# 5-POWER.net
KiCad netlist of a schematic drawn in Altium Designer
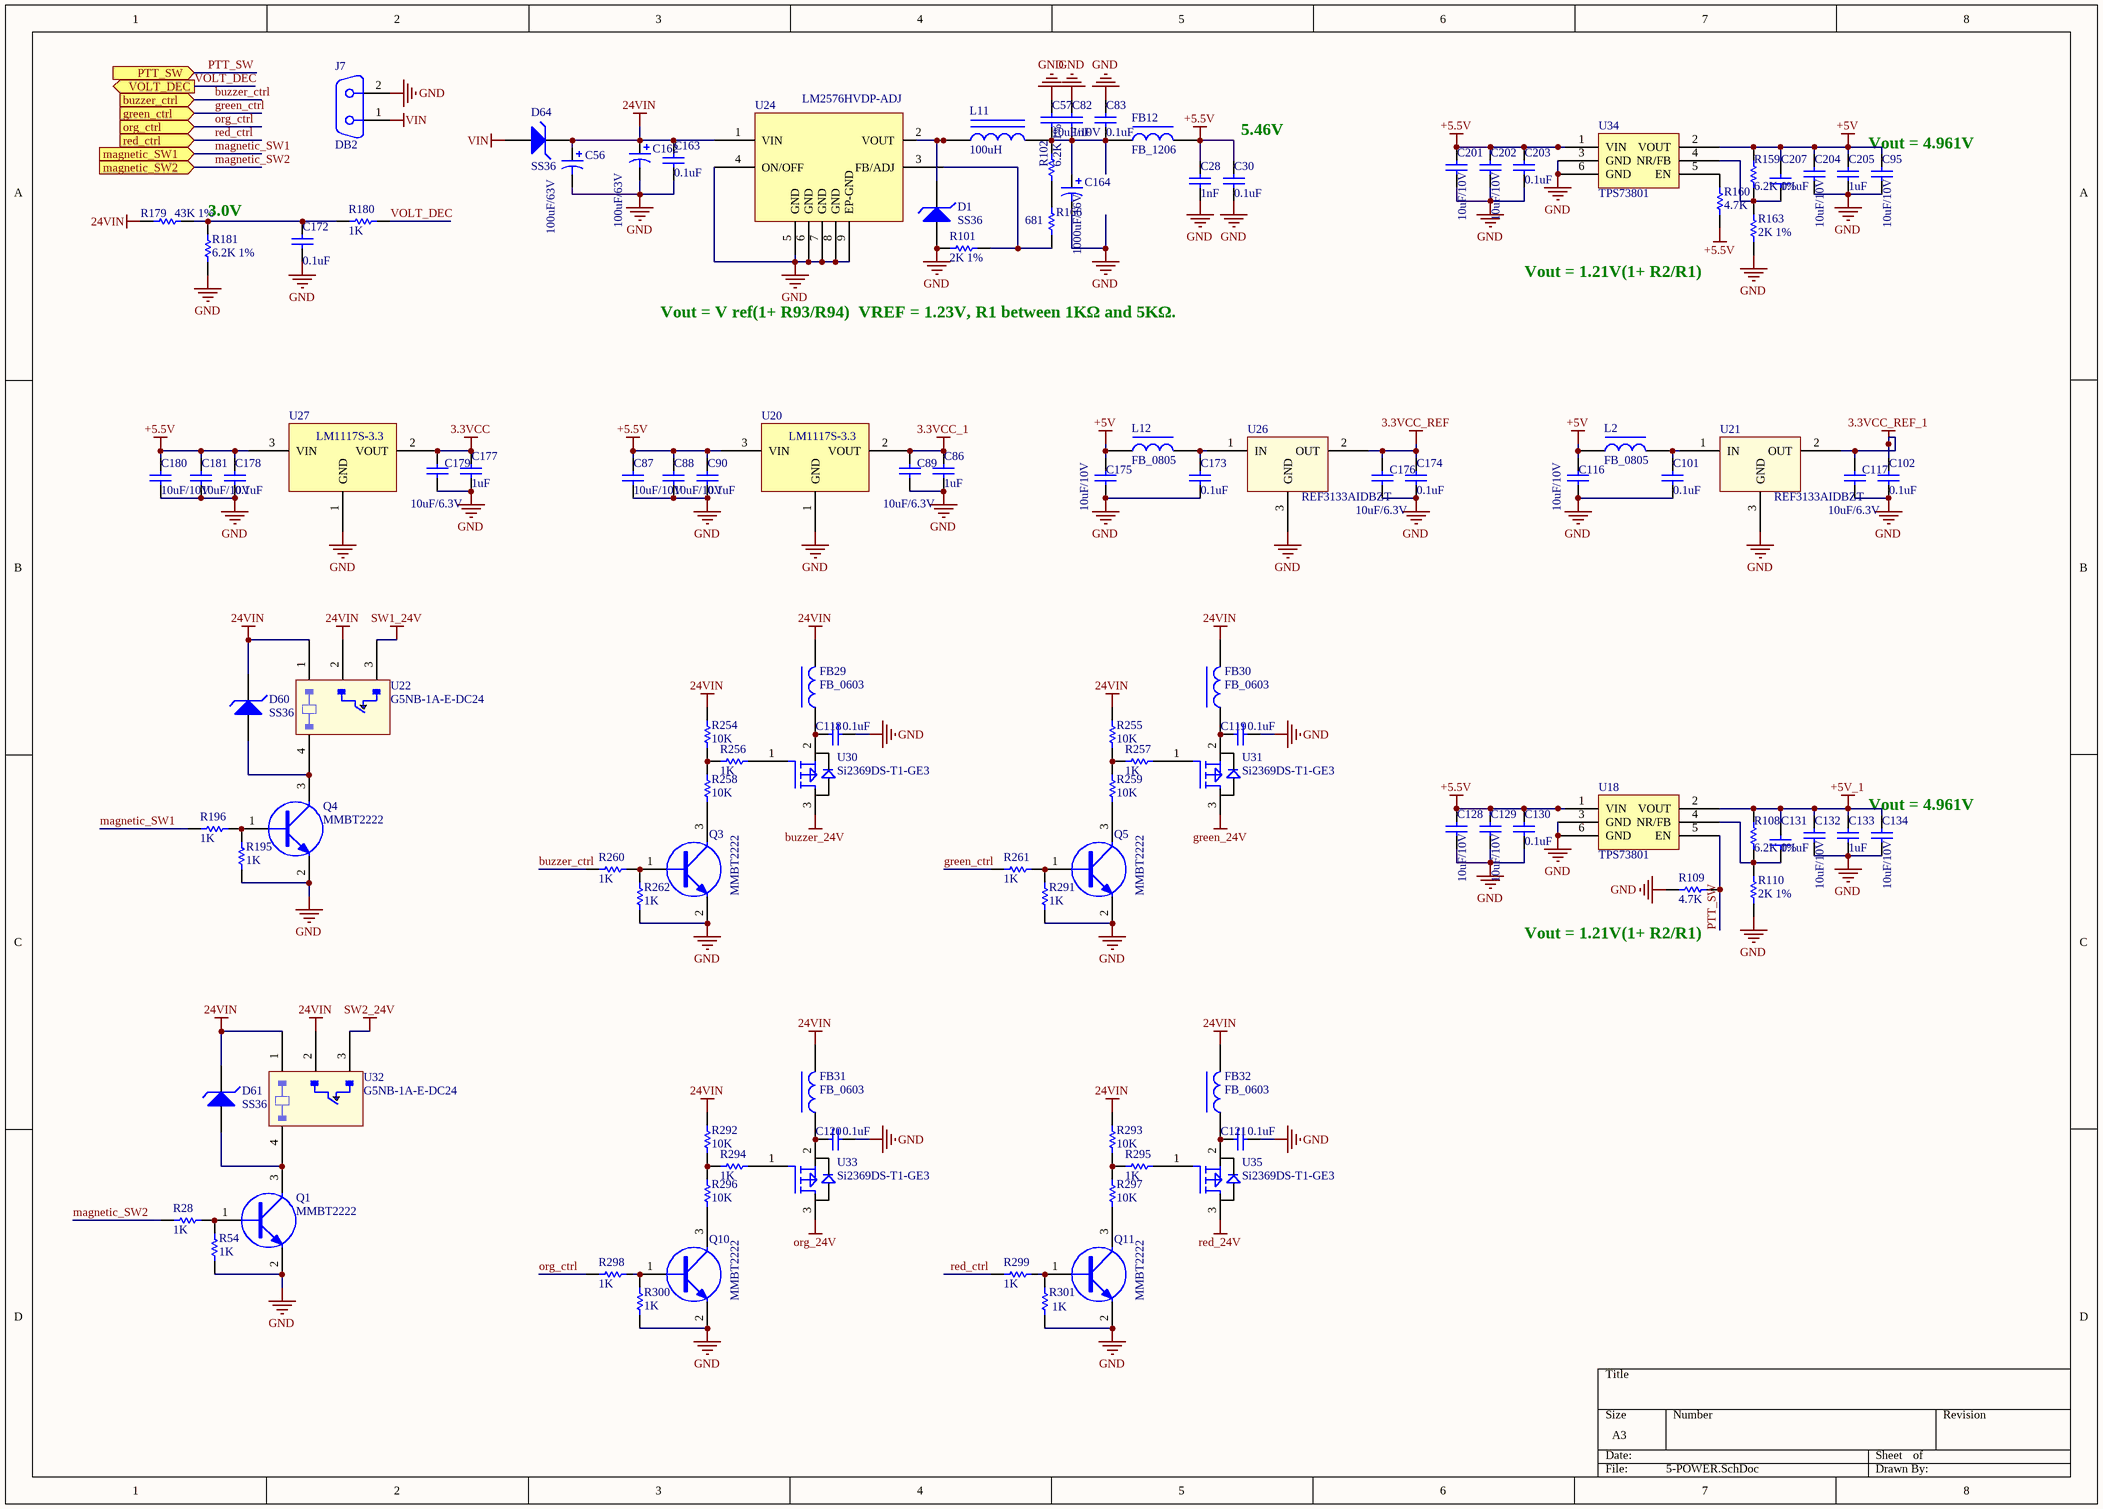
[diagram p0: 5-POWER.SchDoc]

(export (version "E")
  (design (tool "Eeschema 10.0.6"))
  (components
    (comp (ref "C28")
      (value "1nF")
      (footprint "C0603")
      (description "贴片电容_GRM188R71H102KA01_1000pF±10%,50V,0603")
      (libsource (lib "20贴片电容0603") (part "1000pF贴片电容"))
    )
    (comp (ref "C30")
      (value "0.1uF")
      (footprint "C0603")
      (description "GRM188R71H104KA01D")
      (fields (field (name "MPN") "MURATA"))
      (libsource (lib "20贴片电容0603") (part "0.1uF"))
    )
    (comp (ref "C56")
      (value "100uF/63V")
      (footprint "ECAP2SM_10R4x10R4")
      (description "电解电容_VEJ101M1JTR-1010_100uF/63V,±20%,表贴10*10")
      (libsource (lib "23电解电容") (part "100uF/63V电解电容"))
    )
    (comp (ref "C57")
      (value "10uF/10V")
      (footprint "C0805")
      (description "贴片电容_GRM21BR61A106KE19L_10uF±10%,10V,0805")
      (libsource (lib "21贴片电容0805") (part "10uF贴片电容"))
    )
    (comp (ref "C82")
      (value "1nF")
      (footprint "C0603")
      (description "贴片电容_GRM188R71H102KA01_1000pF±10%,50V,0603")
      (libsource (lib "20贴片电容0603") (part "1000pF贴片电容"))
    )
    (comp (ref "C83")
      (value "0.1uF")
      (footprint "C0603")
      (description "GRM188R71H104KA01D")
      (fields (field (name "MPN") "MURATA"))
      (libsource (lib "20贴片电容0603") (part "0.1uF"))
    )
    (comp (ref "C86")
      (value "1uF")
      (footprint "C0603")
      (description "贴片电容_GRM188R61A105KA61D_1uF±10%,10V,0603")
      (libsource (lib "20贴片电容0603") (part "1uF贴片电容"))
    )
    (comp (ref "C87")
      (value "10uF/10V")
      (footprint "C0805")
      (description "贴片电容_GRM21BR61A106KE19L_10uF±10%,10V,0805")
      (libsource (lib "21贴片电容0805") (part "10uF贴片电容"))
    )
    (comp (ref "C88")
      (value "10uF/10V")
      (footprint "C0805")
      (description "贴片电容_GRM21BR61A106KE19L_10uF±10%,10V,0805")
      (libsource (lib "21贴片电容0805") (part "10uF贴片电容"))
    )
    (comp (ref "C89")
      (value "10uF/6.3V")
      (footprint "C0603")
      (description "贴片电容_GRM188R60J106ME47D_10uF±20%,6.3V,0603")
      (libsource (lib "20贴片电容0603") (part "10uF贴片电容"))
    )
    (comp (ref "C90")
      (value "0.1uF")
      (footprint "C0603")
      (description "贴片电容_GRM188R71H104KA01D_0.1uF±10%,50V,0603")
      (libsource (lib "20贴片电容0603") (part "0.1uF贴片电容"))
    )
    (comp (ref "C95")
      (value "10uF/10V")
      (footprint "C0805")
      (description "贴片电容_GRM21BR61A106KE19L_10uF±10%,10V,0805")
      (libsource (lib "21贴片电容0805") (part "10uF贴片电容"))
    )
    (comp (ref "C101")
      (value "0.1uF")
      (footprint "C0603")
      (description "贴片电容_GRM188R71H104KA01D_0.1uF±10%,50V,0603")
      (libsource (lib "20贴片电容0603") (part "0.1uF贴片电容"))
    )
    (comp (ref "C102")
      (value "0.1uF")
      (footprint "C0603")
      (description "贴片电容_GRM188R71H104KA01D_0.1uF±10%,50V,0603")
      (libsource (lib "20贴片电容0603") (part "0.1uF贴片电容"))
    )
    (comp (ref "C116")
      (value "10uF/10V")
      (footprint "pcblib:C0805")
      (description "贴片电容_GRM21BR61A106KE19L_10uF±10%,10V,0805")
      (libsource (lib "21贴片电容0805") (part "10uF贴片电容"))
    )
    (comp (ref "C117")
      (value "10uF/6.3V")
      (footprint "C0603")
      (description "贴片电容_GRM188R60J106ME47D_10uF±20%,6.3V,0603")
      (libsource (lib "20贴片电容0603") (part "10uF贴片电容"))
    )
    (comp (ref "C118")
      (value "0.1uF")
      (footprint "C0603")
      (description "GRM188R71H104KA01D")
      (fields (field (name "MPN") "MURATA"))
      (libsource (lib "20贴片电容0603") (part "0.1uF"))
    )
    (comp (ref "C119")
      (value "0.1uF")
      (footprint "C0603")
      (description "GRM188R71H104KA01D")
      (fields (field (name "MPN") "MURATA"))
      (libsource (lib "20贴片电容0603") (part "0.1uF"))
    )
    (comp (ref "C120")
      (value "0.1uF")
      (footprint "C0603")
      (description "GRM188R71H104KA01D")
      (fields (field (name "MPN") "MURATA"))
      (libsource (lib "20贴片电容0603") (part "0.1uF"))
    )
    (comp (ref "C121")
      (value "0.1uF")
      (footprint "C0603")
      (description "GRM188R71H104KA01D")
      (fields (field (name "MPN") "MURATA"))
      (libsource (lib "20贴片电容0603") (part "0.1uF"))
    )
    (comp (ref "C128")
      (value "10uF/10V")
      (footprint "pcblib:C0805")
      (description "贴片电容_GRM21BR61A106KE19L_10uF±10%,10V,0805")
      (libsource (lib "21贴片电容0805") (part "10uF贴片电容"))
    )
    (comp (ref "C129")
      (value "10uF/10V")
      (footprint "pcblib:C0805")
      (description "贴片电容_GRM21BR61A106KE19L_10uF±10%,10V,0805")
      (libsource (lib "21贴片电容0805") (part "10uF贴片电容"))
    )
    (comp (ref "C130")
      (value "0.1uF")
      (footprint "C0603")
      (description "贴片电容_GRM188R71H104KA01D_0.1uF±10%,50V,0603")
      (libsource (lib "20贴片电容0603") (part "0.1uF贴片电容"))
    )
    (comp (ref "C131")
      (value "0.1uF")
      (footprint "C0603")
      (description "贴片电容_GRM188R71H104KA01D_0.1uF±10%,50V,0603")
      (libsource (lib "20贴片电容0603") (part "0.1uF贴片电容"))
    )
    (comp (ref "C132")
      (value "10uF/10V")
      (footprint "pcblib:C0805")
      (description "贴片电容_GRM21BR61A106KE19L_10uF±10%,10V,0805")
      (libsource (lib "21贴片电容0805") (part "10uF贴片电容"))
    )
    (comp (ref "C133")
      (value "1uF")
      (footprint "C0603")
      (description "贴片电容_GRM188R61A105KA61D_1uF±10%,10V,0603")
      (libsource (lib "20贴片电容0603") (part "1uF贴片电容"))
    )
    (comp (ref "C134")
      (value "10uF/10V")
      (footprint "pcblib:C0805")
      (description "贴片电容_GRM21BR61A106KE19L_10uF±10%,10V,0805")
      (libsource (lib "21贴片电容0805") (part "10uF贴片电容"))
    )
    (comp (ref "C162")
      (value "100uF/63V")
      (footprint "ECAP2SM_10R4x10R4")
      (description "电解电容_VEJ101M1JTR-1010_100uF/63V,±20%,表贴10*10")
      (libsource (lib "23电解电容") (part "100uF/63V电解电容"))
    )
    (comp (ref "C163")
      (value "0.1uF")
      (footprint "C0603")
      (description "贴片电容_GRM188R71H104KA01D_0.1uF±10%,50V,0603")
      (libsource (lib "20贴片电容0603") (part "0.1uF贴片电容"))
    )
    (comp (ref "C164")
      (value "1000uF/16V")
      (footprint "ECAP2SM_10R4x10R4")
      (description "电解电容_VE102M1CTR-1010_1000uF/16V,±20%,表贴10*10")
      (libsource (lib "23电解电容") (part "1000uF/16V电解电容"))
    )
    (comp (ref "C172")
      (value "0.1uF")
      (footprint "C0603")
      (description "贴片电容_GRM188R71H104KA01D_0.1uF±10%,50V,0603")
      (libsource (lib "20贴片电容0603") (part "0.1uF贴片电容"))
    )
    (comp (ref "C173")
      (value "0.1uF")
      (footprint "C0603")
      (description "贴片电容_GRM188R71H104KA01D_0.1uF±10%,50V,0603")
      (libsource (lib "20贴片电容0603") (part "0.1uF贴片电容"))
    )
    (comp (ref "C174")
      (value "0.1uF")
      (footprint "C0603")
      (description "贴片电容_GRM188R71H104KA01D_0.1uF±10%,50V,0603")
      (libsource (lib "20贴片电容0603") (part "0.1uF贴片电容"))
    )
    (comp (ref "C175")
      (value "10uF/10V")
      (footprint "C0805")
      (description "贴片电容_GRM21BR61A106KE19L_10uF±10%,10V,0805")
      (libsource (lib "21贴片电容0805") (part "10uF贴片电容"))
    )
    (comp (ref "C176")
      (value "10uF/6.3V")
      (footprint "C0603")
      (description "贴片电容_GRM188R60J106ME47D_10uF±20%,6.3V,0603")
      (libsource (lib "20贴片电容0603") (part "10uF贴片电容"))
    )
    (comp (ref "C177")
      (value "1uF")
      (footprint "C0603")
      (description "贴片电容_GRM188R61A105KA61D_1uF±10%,10V,0603")
      (libsource (lib "20贴片电容0603") (part "1uF贴片电容"))
    )
    (comp (ref "C178")
      (value "0.1uF")
      (footprint "C0603")
      (description "贴片电容_GRM188R71H104KA01D_0.1uF±10%,50V,0603")
      (libsource (lib "20贴片电容0603") (part "0.1uF贴片电容"))
    )
    (comp (ref "C179")
      (value "10uF/6.3V")
      (footprint "C0603")
      (description "贴片电容_GRM188R60J106ME47D_10uF±20%,6.3V,0603")
      (libsource (lib "20贴片电容0603") (part "10uF贴片电容"))
    )
    (comp (ref "C180")
      (value "10uF/10V")
      (footprint "C0805")
      (description "贴片电容_GRM21BR61A106KE19L_10uF±10%,10V,0805")
      (libsource (lib "21贴片电容0805") (part "10uF贴片电容"))
    )
    (comp (ref "C181")
      (value "10uF/10V")
      (footprint "C0805")
      (description "贴片电容_GRM21BR61A106KE19L_10uF±10%,10V,0805")
      (libsource (lib "21贴片电容0805") (part "10uF贴片电容"))
    )
    (comp (ref "C201")
      (value "10uF/10V")
      (footprint "C0805")
      (description "贴片电容_GRM21BR61A106KE19L_10uF±10%,10V,0805")
      (libsource (lib "21贴片电容0805") (part "10uF贴片电容"))
    )
    (comp (ref "C202")
      (value "10uF/10V")
      (footprint "C0805")
      (description "贴片电容_GRM21BR61A106KE19L_10uF±10%,10V,0805")
      (libsource (lib "21贴片电容0805") (part "10uF贴片电容"))
    )
    (comp (ref "C203")
      (value "0.1uF")
      (footprint "C0603")
      (description "贴片电容_GRM188R71H104KA01D_0.1uF±10%,50V,0603")
      (libsource (lib "20贴片电容0603") (part "0.1uF贴片电容"))
    )
    (comp (ref "C204")
      (value "10uF/10V")
      (footprint "C0805")
      (description "贴片电容_GRM21BR61A106KE19L_10uF±10%,10V,0805")
      (libsource (lib "21贴片电容0805") (part "10uF贴片电容"))
    )
    (comp (ref "C205")
      (value "1uF")
      (footprint "C0603")
      (description "贴片电容_GRM188R61A105KA61D_1uF±10%,10V,0603")
      (libsource (lib "20贴片电容0603") (part "1uF贴片电容"))
    )
    (comp (ref "C207")
      (value "0.1uF")
      (footprint "C0603")
      (description "贴片电容_GRM188R71H104KA01D_0.1uF±10%,50V,0603")
      (libsource (lib "20贴片电容0603") (part "0.1uF贴片电容"))
    )
    (comp (ref "D1")
      (value "SS36")
      (footprint "DO-214AC")
      (description "肖特基整流二极管_SS36_封装SMA,3A/60V")
      (libsource (lib "40二极管") (part "肖特基整流二极管_SS36"))
    )
    (comp (ref "D60")
      (value "SS36")
      (footprint "DO-214AC")
      (description "肖特基整流二极管_SS36_封装SMA,3A/60V")
      (libsource (lib "40二极管") (part "肖特基整流二极管_SS36"))
    )
    (comp (ref "D61")
      (value "SS36")
      (footprint "DO-214AC")
      (description "肖特基整流二极管_SS36_封装SMA,3A/60V")
      (libsource (lib "40二极管") (part "肖特基整流二极管_SS36"))
    )
    (comp (ref "D64")
      (value "SS36")
      (footprint "DO-214AC")
      (description "肖特基整流二极管_SS36_封装SMA,3A/60V")
      (libsource (lib "40二极管") (part "肖特基整流二极管_SS36"))
    )
    (comp (ref "FB12")
      (value "FB_1206")
      (footprint "L1206")
      (description "贴片磁珠_30R,6A,1206")
      (libsource (lib "34贴片磁珠1206") (part "1206贴片磁珠"))
    )
    (comp (ref "FB29")
      (value "FB_0603")
      (footprint "L0603")
      (description "贴片磁珠_100R,0603")
      (libsource (lib "32贴片磁珠0603") (part "0603贴片磁珠"))
    )
    (comp (ref "FB30")
      (value "FB_0603")
      (footprint "L0603")
      (description "贴片磁珠_100R,0603")
      (libsource (lib "32贴片磁珠0603") (part "0603贴片磁珠"))
    )
    (comp (ref "FB31")
      (value "FB_0603")
      (footprint "L0603")
      (description "贴片磁珠_100R,0603")
      (libsource (lib "32贴片磁珠0603") (part "0603贴片磁珠"))
    )
    (comp (ref "FB32")
      (value "FB_0603")
      (footprint "L0603")
      (description "贴片磁珠_100R,0603")
      (libsource (lib "32贴片磁珠0603") (part "0603贴片磁珠"))
    )
    (comp (ref "J7")
      (value "DB2")
      (footprint "DB2TM-VM")
      (description "连接器_DB2公头,电源接头")
      (libsource (lib "91连接器") (part "DB2公头座子"))
    )
    (comp (ref "L2")
      (value "FB_0805")
      (footprint "L0805")
      (description "贴片磁珠_600R,0805")
      (libsource (lib "32贴片磁珠0805") (part "0805贴片磁珠"))
    )
    (comp (ref "L11")
      (value "100uH")
      (footprint "PL2SM-12R5x12R5")
      (description "贴片功率电感_SLF12575T-101M1R9-PF_100uH±20%,额定电流1.9A,12.5x12.5")
      (libsource (lib "32贴片功率电感") (part "100uH贴片功率电感"))
    )
    (comp (ref "L12")
      (value "FB_0805")
      (footprint "L0805")
      (description "贴片磁珠_600R,0805")
      (libsource (lib "32贴片磁珠0805") (part "0805贴片磁珠"))
    )
    (comp (ref "Q1")
      (value "MMBT2222")
      (footprint "SOT23-3")
      (description "NPN三极管_MMBT2222_表贴SOT23")
      (libsource (lib "50三极管") (part "MMBT2222"))
    )
    (comp (ref "Q3")
      (value "MMBT2222")
      (footprint "SOT23-3")
      (description "NPN三极管_MMBT2222_表贴SOT23")
      (libsource (lib "50三极管") (part "MMBT2222"))
    )
    (comp (ref "Q4")
      (value "MMBT2222")
      (footprint "SOT23-3")
      (description "NPN三极管_MMBT2222_表贴SOT23")
      (libsource (lib "50三极管") (part "MMBT2222"))
    )
    (comp (ref "Q5")
      (value "MMBT2222")
      (footprint "SOT23-3")
      (description "NPN三极管_MMBT2222_表贴SOT23")
      (libsource (lib "50三极管") (part "MMBT2222"))
    )
    (comp (ref "Q10")
      (value "MMBT2222")
      (footprint "SOT23-3")
      (description "NPN三极管_MMBT2222_表贴SOT23")
      (libsource (lib "50三极管") (part "MMBT2222"))
    )
    (comp (ref "Q11")
      (value "MMBT2222")
      (footprint "SOT23-3")
      (description "NPN三极管_MMBT2222_表贴SOT23")
      (libsource (lib "50三极管") (part "MMBT2222"))
    )
    (comp (ref "R28")
      (value "1K")
      (footprint "R0603")
      (description "贴片电阻_1K±5%,0603")
      (libsource (lib "10贴片电阻0603") (part "1K贴片电阻"))
    )
    (comp (ref "R54")
      (value "1K")
      (footprint "R0603")
      (description "贴片电阻_1K±5%,0603")
      (libsource (lib "10贴片电阻0603") (part "1K贴片电阻"))
    )
    (comp (ref "R101")
      (value "2K 1%")
      (footprint "R0603")
      (description "贴片电阻_2K±5%,0603")
      (libsource (lib "10贴片电阻0603") (part "2K贴片电阻"))
    )
    (comp (ref "R102")
      (value "6.2K 1%")
      (footprint "R0603")
      (description "贴片电阻_6.2K±5%,0603")
      (libsource (lib "10贴片电阻0603") (part "6.2K贴片电阻"))
    )
    (comp (ref "R108")
      (value "6.2K 1%")
      (footprint "R0603")
      (description "贴片电阻_6.2K±5%,0603")
      (libsource (lib "10贴片电阻0603") (part "6.2K贴片电阻"))
    )
    (comp (ref "R109")
      (value "4.7K")
      (footprint "R0603")
      (description "贴片电阻_4.7K±5%,0603")
      (libsource (lib "10贴片电阻0603") (part "4.7K贴片电阻"))
    )
    (comp (ref "R110")
      (value "2K 1%")
      (footprint "R0603")
      (description "贴片电阻_2K±5%,0603")
      (libsource (lib "10贴片电阻0603") (part "2K贴片电阻"))
    )
    (comp (ref "R159")
      (value "6.2K 1%")
      (footprint "R0603")
      (description "贴片电阻_6.2K±5%,0603")
      (libsource (lib "10贴片电阻0603") (part "6.2K贴片电阻"))
    )
    (comp (ref "R160")
      (value "4.7K")
      (footprint "R0603")
      (description "贴片电阻_4.7K±5%,0603")
      (libsource (lib "10贴片电阻0603") (part "4.7K贴片电阻"))
    )
    (comp (ref "R163")
      (value "2K 1%")
      (footprint "R0603")
      (description "贴片电阻_2K±5%,0603")
      (libsource (lib "10贴片电阻0603") (part "2K贴片电阻"))
    )
    (comp (ref "R166")
      (value "681")
      (footprint "R0603")
      (description "0603,681Ω,±1％")
      (libsource (lib "10贴片电阻0603") (part "1.5K贴片电阻"))
    )
    (comp (ref "R179")
      (value "43K 1%")
      (footprint "R0603")
      (description "贴片电阻_12.4K±1%,0603")
      (libsource (lib "10贴片电阻0603") (part "12.4K贴片电阻"))
    )
    (comp (ref "R180")
      (value "1K")
      (footprint "R0603")
      (description "贴片电阻_1K±5%,0603")
      (libsource (lib "10贴片电阻0603") (part "1K贴片电阻"))
    )
    (comp (ref "R181")
      (value "6.2K 1%")
      (footprint "R0603")
      (description "贴片电阻_1.5K±5%,0603")
      (libsource (lib "10贴片电阻0603") (part "1.5K贴片电阻"))
    )
    (comp (ref "R195")
      (value "1K")
      (footprint "R0603")
      (description "贴片电阻_1K±5%,0603")
      (libsource (lib "10贴片电阻0603") (part "1K贴片电阻"))
    )
    (comp (ref "R196")
      (value "1K")
      (footprint "R0603")
      (description "贴片电阻_1K±5%,0603")
      (libsource (lib "10贴片电阻0603") (part "1K贴片电阻"))
    )
    (comp (ref "R254")
      (value "10K")
      (footprint "R0603")
      (description "贴片电阻_1K±5%,0603")
      (libsource (lib "10贴片电阻0603") (part "1K贴片电阻"))
    )
    (comp (ref "R255")
      (value "10K")
      (footprint "R0603")
      (description "贴片电阻_1K±5%,0603")
      (libsource (lib "10贴片电阻0603") (part "1K贴片电阻"))
    )
    (comp (ref "R256")
      (value "1K")
      (footprint "R0603")
      (description "贴片电阻_1K±5%,0603")
      (libsource (lib "10贴片电阻0603") (part "1K贴片电阻"))
    )
    (comp (ref "R257")
      (value "1K")
      (footprint "R0603")
      (description "贴片电阻_1K±5%,0603")
      (libsource (lib "10贴片电阻0603") (part "1K贴片电阻"))
    )
    (comp (ref "R258")
      (value "10K")
      (footprint "R0603")
      (description "贴片电阻_1K±5%,0603")
      (libsource (lib "10贴片电阻0603") (part "1K贴片电阻"))
    )
    (comp (ref "R259")
      (value "10K")
      (footprint "R0603")
      (description "贴片电阻_1K±5%,0603")
      (libsource (lib "10贴片电阻0603") (part "1K贴片电阻"))
    )
    (comp (ref "R260")
      (value "1K")
      (footprint "R0603")
      (description "贴片电阻_1K±5%,0603")
      (libsource (lib "10贴片电阻0603") (part "1K贴片电阻"))
    )
    (comp (ref "R261")
      (value "1K")
      (footprint "R0603")
      (description "贴片电阻_1K±5%,0603")
      (libsource (lib "10贴片电阻0603") (part "1K贴片电阻"))
    )
    (comp (ref "R262")
      (value "1K")
      (footprint "R0603")
      (description "贴片电阻_1K±5%,0603")
      (libsource (lib "10贴片电阻0603") (part "1K贴片电阻"))
    )
    (comp (ref "R291")
      (value "1K")
      (footprint "R0603")
      (description "贴片电阻_1K±5%,0603")
      (libsource (lib "10贴片电阻0603") (part "1K贴片电阻"))
    )
    (comp (ref "R292")
      (value "10K")
      (footprint "R0603")
      (description "贴片电阻_1K±5%,0603")
      (libsource (lib "10贴片电阻0603") (part "1K贴片电阻"))
    )
    (comp (ref "R293")
      (value "10K")
      (footprint "R0603")
      (description "贴片电阻_1K±5%,0603")
      (libsource (lib "10贴片电阻0603") (part "1K贴片电阻"))
    )
    (comp (ref "R294")
      (value "1K")
      (footprint "R0603")
      (description "贴片电阻_1K±5%,0603")
      (libsource (lib "10贴片电阻0603") (part "1K贴片电阻"))
    )
    (comp (ref "R295")
      (value "1K")
      (footprint "R0603")
      (description "贴片电阻_1K±5%,0603")
      (libsource (lib "10贴片电阻0603") (part "1K贴片电阻"))
    )
    (comp (ref "R296")
      (value "10K")
      (footprint "R0603")
      (description "贴片电阻_1K±5%,0603")
      (libsource (lib "10贴片电阻0603") (part "1K贴片电阻"))
    )
    (comp (ref "R297")
      (value "10K")
      (footprint "R0603")
      (description "贴片电阻_1K±5%,0603")
      (libsource (lib "10贴片电阻0603") (part "1K贴片电阻"))
    )
    (comp (ref "R298")
      (value "1K")
      (footprint "R0603")
      (description "贴片电阻_1K±5%,0603")
      (libsource (lib "10贴片电阻0603") (part "1K贴片电阻"))
    )
    (comp (ref "R299")
      (value "1K")
      (footprint "R0603")
      (description "贴片电阻_1K±5%,0603")
      (libsource (lib "10贴片电阻0603") (part "1K贴片电阻"))
    )
    (comp (ref "R300")
      (value "1K")
      (footprint "R0603")
      (description "贴片电阻_1K±5%,0603")
      (libsource (lib "10贴片电阻0603") (part "1K贴片电阻"))
    )
    (comp (ref "R301")
      (value "1K")
      (footprint "R0603")
      (description "贴片电阻_1K±5%,0603")
      (libsource (lib "10贴片电阻0603") (part "1K贴片电阻"))
    )
    (comp (ref "U18")
      (value "TPS73801")
      (footprint "SOT-223-6")
      (description "LDO_TPS73701DCQ_1A输出,SOT223-6")
      (libsource (lib "78电源芯片") (part "TPS73701DCQ"))
    )
    (comp (ref "U20")
      (value "LM1117S-3.3")
      (footprint "SOT-223")
      (description "LDO_LM1117S-3.3_1A输出,SOT223")
      (libsource (lib "78电源芯片") (part "LM1117S-3.3"))
    )
    (comp (ref "U21")
      (value "REF3133AIDBZT")
      (footprint "SOT23-3")
      (description "LDO_REF3133AIDBZT_3.3V输出,10mA输出,SOT23-3")
      (libsource (lib "78电源芯片") (part "REF3133AIDBZT"))
    )
    (comp (ref "U22")
      (value "G5NB-1A-E-DC24")
      (footprint "G5NB-1A-E-DC24-20R4X7")
      (description "继电器_G5NB-1A-E-DC24")
      (libsource (lib "94继电器") (part "G5NB-1A-E-DC24"))
    )
    (comp (ref "U24")
      (value "LM2576HVDP-ADJ")
      (footprint "SOIC8_1R27_3R9x4R9-1")
      (description "稳压集成电路_LM2576HVDP-ADJ_3A输出,SOIC8")
      (libsource (lib "78电源芯片") (part "LM2576HVDP-ADJ"))
    )
    (comp (ref "U26")
      (value "REF3133AIDBZT")
      (footprint "SOT23-3")
      (description "LDO_REF3133AIDBZT_3.3V输出,10mA输出,SOT23-3")
      (libsource (lib "78电源芯片") (part "REF3133AIDBZT"))
    )
    (comp (ref "U27")
      (value "LM1117S-3.3")
      (footprint "SOT-223")
      (description "LDO_LM1117S-3.3_1A输出,SOT223")
      (libsource (lib "78电源芯片") (part "LM1117S-3.3"))
    )
    (comp (ref "U30")
      (value "Si2369DS-T1-GE3")
      (footprint "SOT23-3")
      (description "P-MOS_Si2369DS-T1-GE3_SOT23")
      (libsource (lib "51场效应管") (part "Si2369DS-T1-GE3"))
    )
    (comp (ref "U31")
      (value "Si2369DS-T1-GE3")
      (footprint "SOT23-3")
      (description "P-MOS_Si2369DS-T1-GE3_SOT23")
      (libsource (lib "51场效应管") (part "Si2369DS-T1-GE3"))
    )
    (comp (ref "U32")
      (value "G5NB-1A-E-DC24")
      (footprint "G5NB-1A-E-DC24-20R4X7")
      (description "继电器_G5NB-1A-E-DC24")
      (libsource (lib "94继电器") (part "G5NB-1A-E-DC24"))
    )
    (comp (ref "U33")
      (value "Si2369DS-T1-GE3")
      (footprint "SOT23-3")
      (description "P-MOS_Si2369DS-T1-GE3_SOT23")
      (libsource (lib "51场效应管") (part "Si2369DS-T1-GE3"))
    )
    (comp (ref "U34")
      (value "TPS73801")
      (footprint "SOT-223-6")
      (description "LDO_TPS73701DCQ_1A输出,SOT223-6")
      (libsource (lib "78电源芯片") (part "TPS73701DCQ"))
    )
    (comp (ref "U35")
      (value "Si2369DS-T1-GE3")
      (footprint "SOT23-3")
      (description "P-MOS_Si2369DS-T1-GE3_SOT23")
      (libsource (lib "51场效应管") (part "Si2369DS-T1-GE3"))
    )
  )
  (nets
    (net (code "1") (name "+5.5V") (class "Default")
      (node (ref "C128") (pin "2") (pinfunction "2_2") (pintype "passive"))
      (node (ref "C129") (pin "2") (pinfunction "2_2") (pintype "passive"))
      (node (ref "C130") (pin "2") (pinfunction "2_2") (pintype "passive"))
      (node (ref "C178") (pin "2") (pinfunction "2_2") (pintype "passive"))
      (node (ref "C180") (pin "2") (pinfunction "2_2") (pintype "passive"))
      (node (ref "C181") (pin "2") (pinfunction "2_2") (pintype "passive"))
      (node (ref "C201") (pin "2") (pinfunction "2_2") (pintype "passive"))
      (node (ref "C202") (pin "2") (pinfunction "2_2") (pintype "passive"))
      (node (ref "C203") (pin "2") (pinfunction "2_2") (pintype "passive"))
      (node (ref "C28") (pin "2") (pinfunction "2_2") (pintype "passive"))
      (node (ref "C30") (pin "2") (pinfunction "2_2") (pintype "passive"))
      (node (ref "C87") (pin "2") (pinfunction "2_2") (pintype "passive"))
      (node (ref "C88") (pin "2") (pinfunction "2_2") (pintype "passive"))
      (node (ref "C90") (pin "2") (pinfunction "2_2") (pintype "passive"))
      (node (ref "FB12") (pin "2") (pinfunction "2_2") (pintype "passive"))
      (node (ref "R160") (pin "2") (pinfunction "2_2") (pintype "passive"))
      (node (ref "U18") (pin "1") (pinfunction "VIN_1") (pintype "passive"))
      (node (ref "U20") (pin "3") (pinfunction "VIN_3") (pintype "passive"))
      (node (ref "U27") (pin "3") (pinfunction "VIN_3") (pintype "passive"))
      (node (ref "U34") (pin "1") (pinfunction "VIN_1") (pintype "passive"))
    )
    (net (code "2") (name "+5V") (class "Default")
      (node (ref "C116") (pin "2") (pinfunction "2_2") (pintype "passive"))
      (node (ref "C175") (pin "2") (pinfunction "2_2") (pintype "passive"))
      (node (ref "C204") (pin "2") (pinfunction "2_2") (pintype "passive"))
      (node (ref "C205") (pin "2") (pinfunction "2_2") (pintype "passive"))
      (node (ref "C207") (pin "2") (pinfunction "2_2") (pintype "passive"))
      (node (ref "C95") (pin "2") (pinfunction "2_2") (pintype "passive"))
      (node (ref "L12") (pin "1") (pinfunction "1_1") (pintype "passive"))
      (node (ref "L2") (pin "1") (pinfunction "1_1") (pintype "passive"))
      (node (ref "R159") (pin "2") (pinfunction "2_2") (pintype "passive"))
      (node (ref "U34") (pin "2") (pinfunction "VOUT_2") (pintype "passive"))
    )
    (net (code "3") (name "+5V_1") (class "Default")
      (node (ref "C131") (pin "2") (pinfunction "2_2") (pintype "passive"))
      (node (ref "C132") (pin "2") (pinfunction "2_2") (pintype "passive"))
      (node (ref "C133") (pin "2") (pinfunction "2_2") (pintype "passive"))
      (node (ref "C134") (pin "2") (pinfunction "2_2") (pintype "passive"))
      (node (ref "R108") (pin "2") (pinfunction "2_2") (pintype "passive"))
      (node (ref "U18") (pin "2") (pinfunction "VOUT_2") (pintype "passive"))
    )
    (net (code "4") (name "/PTT_SW") (class "Default")
      (node (ref "R109") (pin "2") (pinfunction "2_2") (pintype "passive"))
      (node (ref "U18") (pin "5") (pinfunction "EN_5") (pintype "passive"))
    )
    (net (code "5") (name "/VOLT_DEC") (class "Default")
      (node (ref "R180") (pin "1") (pinfunction "1_1") (pintype "passive"))
    )
    (net (code "6") (name "/buzzer_ctrl") (class "Default")
      (node (ref "R260") (pin "1") (pinfunction "1_1") (pintype "passive"))
    )
    (net (code "7") (name "/green_ctrl") (class "Default")
      (node (ref "R261") (pin "1") (pinfunction "1_1") (pintype "passive"))
    )
    (net (code "8") (name "/magnetic_SW1") (class "Default")
      (node (ref "R196") (pin "1") (pinfunction "1_1") (pintype "passive"))
    )
    (net (code "9") (name "/magnetic_SW2") (class "Default")
      (node (ref "R28") (pin "1") (pinfunction "1_1") (pintype "passive"))
    )
    (net (code "10") (name "/org_ctrl") (class "Default")
      (node (ref "R298") (pin "1") (pinfunction "1_1") (pintype "passive"))
    )
    (net (code "11") (name "/red_ctrl") (class "Default")
      (node (ref "R299") (pin "1") (pinfunction "1_1") (pintype "passive"))
    )
    (net (code "12") (name "3.3VCC") (class "Default")
      (node (ref "C177") (pin "2") (pinfunction "2_2") (pintype "passive"))
      (node (ref "C179") (pin "2") (pinfunction "2_2") (pintype "passive"))
      (node (ref "U27") (pin "2") (pinfunction "VOUT_2") (pintype "passive"))
    )
    (net (code "13") (name "3.3VCC_1") (class "Default")
      (node (ref "C86") (pin "2") (pinfunction "2_2") (pintype "passive"))
      (node (ref "C89") (pin "2") (pinfunction "2_2") (pintype "passive"))
      (node (ref "U20") (pin "2") (pinfunction "VOUT_2") (pintype "passive"))
    )
    (net (code "14") (name "3.3VCC_REF") (class "Default")
      (node (ref "C174") (pin "2") (pinfunction "2_2") (pintype "passive"))
      (node (ref "C176") (pin "2") (pinfunction "2_2") (pintype "passive"))
      (node (ref "U26") (pin "2") (pinfunction "OUT_2") (pintype "passive"))
    )
    (net (code "15") (name "3.3VCC_REF_1") (class "Default")
      (node (ref "C102") (pin "2") (pinfunction "2_2") (pintype "passive"))
      (node (ref "C117") (pin "2") (pinfunction "2_2") (pintype "passive"))
      (node (ref "U21") (pin "2") (pinfunction "OUT_2") (pintype "passive"))
    )
    (net (code "16") (name "24VIN") (class "Default")
      (node (ref "C162") (pin "1") (pinfunction "1_1") (pintype "passive"))
      (node (ref "C163") (pin "2") (pinfunction "2_2") (pintype "passive"))
      (node (ref "C56") (pin "1") (pinfunction "1_1") (pintype "passive"))
      (node (ref "D60") (pin "2") (pinfunction "K_2") (pintype "passive"))
      (node (ref "D61") (pin "2") (pinfunction "K_2") (pintype "passive"))
      (node (ref "D64") (pin "2") (pinfunction "K_2") (pintype "passive"))
      (node (ref "FB29") (pin "2") (pinfunction "2_2") (pintype "passive"))
      (node (ref "FB30") (pin "2") (pinfunction "2_2") (pintype "passive"))
      (node (ref "FB31") (pin "2") (pinfunction "2_2") (pintype "passive"))
      (node (ref "FB32") (pin "2") (pinfunction "2_2") (pintype "passive"))
      (node (ref "R179") (pin "1") (pinfunction "1_1") (pintype "passive"))
      (node (ref "R254") (pin "2") (pinfunction "2_2") (pintype "passive"))
      (node (ref "R255") (pin "2") (pinfunction "2_2") (pintype "passive"))
      (node (ref "R292") (pin "2") (pinfunction "2_2") (pintype "passive"))
      (node (ref "R293") (pin "2") (pinfunction "2_2") (pintype "passive"))
      (node (ref "U22") (pin "1") (pinfunction "1_1") (pintype "passive"))
      (node (ref "U22") (pin "2") (pinfunction "2_2") (pintype "passive"))
      (node (ref "U24") (pin "1") (pinfunction "VIN_1") (pintype "passive"))
      (node (ref "U32") (pin "1") (pinfunction "1_1") (pintype "passive"))
      (node (ref "U32") (pin "2") (pinfunction "2_2") (pintype "passive"))
    )
    (net (code "17") (name "GND") (class "Default")
      (node (ref "C101") (pin "1") (pinfunction "1_1") (pintype "passive"))
      (node (ref "C102") (pin "1") (pinfunction "1_1") (pintype "passive"))
      (node (ref "C116") (pin "1") (pinfunction "1_1") (pintype "passive"))
      (node (ref "C117") (pin "1") (pinfunction "1_1") (pintype "passive"))
      (node (ref "C118") (pin "1") (pinfunction "1_1") (pintype "passive"))
      (node (ref "C119") (pin "1") (pinfunction "1_1") (pintype "passive"))
      (node (ref "C120") (pin "1") (pinfunction "1_1") (pintype "passive"))
      (node (ref "C121") (pin "1") (pinfunction "1_1") (pintype "passive"))
      (node (ref "C128") (pin "1") (pinfunction "1_1") (pintype "passive"))
      (node (ref "C129") (pin "1") (pinfunction "1_1") (pintype "passive"))
      (node (ref "C130") (pin "1") (pinfunction "1_1") (pintype "passive"))
      (node (ref "C132") (pin "1") (pinfunction "1_1") (pintype "passive"))
      (node (ref "C133") (pin "1") (pinfunction "1_1") (pintype "passive"))
      (node (ref "C134") (pin "1") (pinfunction "1_1") (pintype "passive"))
      (node (ref "C162") (pin "2") (pinfunction "2_2") (pintype "passive"))
      (node (ref "C163") (pin "1") (pinfunction "1_1") (pintype "passive"))
      (node (ref "C164") (pin "2") (pinfunction "2_2") (pintype "passive"))
      (node (ref "C172") (pin "1") (pinfunction "1_1") (pintype "passive"))
      (node (ref "C173") (pin "1") (pinfunction "1_1") (pintype "passive"))
      (node (ref "C174") (pin "1") (pinfunction "1_1") (pintype "passive"))
      (node (ref "C175") (pin "1") (pinfunction "1_1") (pintype "passive"))
      (node (ref "C176") (pin "1") (pinfunction "1_1") (pintype "passive"))
      (node (ref "C177") (pin "1") (pinfunction "1_1") (pintype "passive"))
      (node (ref "C178") (pin "1") (pinfunction "1_1") (pintype "passive"))
      (node (ref "C179") (pin "1") (pinfunction "1_1") (pintype "passive"))
      (node (ref "C180") (pin "1") (pinfunction "1_1") (pintype "passive"))
      (node (ref "C181") (pin "1") (pinfunction "1_1") (pintype "passive"))
      (node (ref "C201") (pin "1") (pinfunction "1_1") (pintype "passive"))
      (node (ref "C202") (pin "1") (pinfunction "1_1") (pintype "passive"))
      (node (ref "C203") (pin "1") (pinfunction "1_1") (pintype "passive"))
      (node (ref "C204") (pin "1") (pinfunction "1_1") (pintype "passive"))
      (node (ref "C205") (pin "1") (pinfunction "1_1") (pintype "passive"))
      (node (ref "C28") (pin "1") (pinfunction "1_1") (pintype "passive"))
      (node (ref "C30") (pin "1") (pinfunction "1_1") (pintype "passive"))
      (node (ref "C56") (pin "2") (pinfunction "2_2") (pintype "passive"))
      (node (ref "C57") (pin "2") (pinfunction "2_2") (pintype "passive"))
      (node (ref "C82") (pin "2") (pinfunction "2_2") (pintype "passive"))
      (node (ref "C83") (pin "2") (pinfunction "2_2") (pintype "passive"))
      (node (ref "C86") (pin "1") (pinfunction "1_1") (pintype "passive"))
      (node (ref "C87") (pin "1") (pinfunction "1_1") (pintype "passive"))
      (node (ref "C88") (pin "1") (pinfunction "1_1") (pintype "passive"))
      (node (ref "C89") (pin "1") (pinfunction "1_1") (pintype "passive"))
      (node (ref "C90") (pin "1") (pinfunction "1_1") (pintype "passive"))
      (node (ref "C95") (pin "1") (pinfunction "1_1") (pintype "passive"))
      (node (ref "D1") (pin "1") (pinfunction "A_1") (pintype "passive"))
      (node (ref "J7") (pin "2") (pinfunction "2_2") (pintype "passive"))
      (node (ref "Q1") (pin "2") (pinfunction "E_2") (pintype "passive"))
      (node (ref "Q10") (pin "2") (pinfunction "E_2") (pintype "passive"))
      (node (ref "Q11") (pin "2") (pinfunction "E_2") (pintype "passive"))
      (node (ref "Q3") (pin "2") (pinfunction "E_2") (pintype "passive"))
      (node (ref "Q4") (pin "2") (pinfunction "E_2") (pintype "passive"))
      (node (ref "Q5") (pin "2") (pinfunction "E_2") (pintype "passive"))
      (node (ref "R101") (pin "2") (pinfunction "2_2") (pintype "passive"))
      (node (ref "R109") (pin "1") (pinfunction "1_1") (pintype "passive"))
      (node (ref "R110") (pin "1") (pinfunction "1_1") (pintype "passive"))
      (node (ref "R163") (pin "1") (pinfunction "1_1") (pintype "passive"))
      (node (ref "R181") (pin "1") (pinfunction "1_1") (pintype "passive"))
      (node (ref "R195") (pin "1") (pinfunction "1_1") (pintype "passive"))
      (node (ref "R262") (pin "2") (pinfunction "2_2") (pintype "passive"))
      (node (ref "R291") (pin "2") (pinfunction "2_2") (pintype "passive"))
      (node (ref "R300") (pin "2") (pinfunction "2_2") (pintype "passive"))
      (node (ref "R301") (pin "2") (pinfunction "2_2") (pintype "passive"))
      (node (ref "R54") (pin "1") (pinfunction "1_1") (pintype "passive"))
      (node (ref "U18") (pin "3") (pinfunction "GND_3") (pintype "passive"))
      (node (ref "U18") (pin "6") (pinfunction "GND_6") (pintype "passive"))
      (node (ref "U20") (pin "1") (pinfunction "GND_1") (pintype "passive"))
      (node (ref "U21") (pin "3") (pinfunction "GND_3") (pintype "passive"))
      (node (ref "U24") (pin "4") (pinfunction "ON/OFF_4") (pintype "passive"))
      (node (ref "U24") (pin "5") (pinfunction "GND_5") (pintype "passive"))
      (node (ref "U24") (pin "6") (pinfunction "GND_6") (pintype "passive"))
      (node (ref "U24") (pin "7") (pinfunction "GND_7") (pintype "passive"))
      (node (ref "U24") (pin "8") (pinfunction "GND_8") (pintype "passive"))
      (node (ref "U24") (pin "9") (pinfunction "EP-GND_9") (pintype "passive"))
      (node (ref "U26") (pin "3") (pinfunction "GND_3") (pintype "passive"))
      (node (ref "U27") (pin "1") (pinfunction "GND_1") (pintype "passive"))
      (node (ref "U34") (pin "3") (pinfunction "GND_3") (pintype "passive"))
      (node (ref "U34") (pin "6") (pinfunction "GND_6") (pintype "passive"))
    )
    (net (code "18") (name "Net-(C164-Pad1)") (class "Default")
      (node (ref "C164") (pin "1") (pinfunction "1_1") (pintype "passive"))
      (node (ref "C57") (pin "1") (pinfunction "1_1") (pintype "passive"))
      (node (ref "C82") (pin "1") (pinfunction "1_1") (pintype "passive"))
      (node (ref "C83") (pin "1") (pinfunction "1_1") (pintype "passive"))
      (node (ref "FB12") (pin "1") (pinfunction "1_1") (pintype "passive"))
      (node (ref "L11") (pin "2") (pinfunction "2_2") (pintype "passive"))
      (node (ref "R102") (pin "2") (pinfunction "2_2") (pintype "passive"))
    )
    (net (code "19") (name "Net-(C172-Pad2)") (class "Default")
      (node (ref "C172") (pin "2") (pinfunction "2_2") (pintype "passive"))
      (node (ref "R179") (pin "2") (pinfunction "2_2") (pintype "passive"))
      (node (ref "R180") (pin "2") (pinfunction "2_2") (pintype "passive"))
      (node (ref "R181") (pin "2") (pinfunction "2_2") (pintype "passive"))
    )
    (net (code "20") (name "Net-(D1-K)") (class "Default")
      (node (ref "D1") (pin "2") (pinfunction "K_2") (pintype "passive"))
      (node (ref "L11") (pin "1") (pinfunction "1_1") (pintype "passive"))
      (node (ref "U24") (pin "2") (pinfunction "VOUT_2") (pintype "passive"))
    )
    (net (code "21") (name "Net-(D60-A)") (class "Default")
      (node (ref "D60") (pin "1") (pinfunction "A_1") (pintype "passive"))
      (node (ref "Q4") (pin "3") (pinfunction "C_3") (pintype "passive"))
      (node (ref "U22") (pin "4") (pinfunction "4_4") (pintype "passive"))
    )
    (net (code "22") (name "Net-(D61-A)") (class "Default")
      (node (ref "D61") (pin "1") (pinfunction "A_1") (pintype "passive"))
      (node (ref "Q1") (pin "3") (pinfunction "C_3") (pintype "passive"))
      (node (ref "U32") (pin "4") (pinfunction "4_4") (pintype "passive"))
    )
    (net (code "23") (name "Net-(Q1-B)") (class "Default")
      (node (ref "Q1") (pin "1") (pinfunction "B_1") (pintype "passive"))
      (node (ref "R28") (pin "2") (pinfunction "2_2") (pintype "passive"))
      (node (ref "R54") (pin "2") (pinfunction "2_2") (pintype "passive"))
    )
    (net (code "24") (name "Net-(Q3-B)") (class "Default")
      (node (ref "Q3") (pin "1") (pinfunction "B_1") (pintype "passive"))
      (node (ref "R260") (pin "2") (pinfunction "2_2") (pintype "passive"))
      (node (ref "R262") (pin "1") (pinfunction "1_1") (pintype "passive"))
    )
    (net (code "25") (name "Net-(Q3-C)") (class "Default")
      (node (ref "Q3") (pin "3") (pinfunction "C_3") (pintype "passive"))
      (node (ref "R258") (pin "1") (pinfunction "1_1") (pintype "passive"))
    )
    (net (code "26") (name "Net-(Q4-B)") (class "Default")
      (node (ref "Q4") (pin "1") (pinfunction "B_1") (pintype "passive"))
      (node (ref "R195") (pin "2") (pinfunction "2_2") (pintype "passive"))
      (node (ref "R196") (pin "2") (pinfunction "2_2") (pintype "passive"))
    )
    (net (code "27") (name "Net-(Q5-B)") (class "Default")
      (node (ref "Q5") (pin "1") (pinfunction "B_1") (pintype "passive"))
      (node (ref "R261") (pin "2") (pinfunction "2_2") (pintype "passive"))
      (node (ref "R291") (pin "1") (pinfunction "1_1") (pintype "passive"))
    )
    (net (code "28") (name "Net-(Q5-C)") (class "Default")
      (node (ref "Q5") (pin "3") (pinfunction "C_3") (pintype "passive"))
      (node (ref "R259") (pin "1") (pinfunction "1_1") (pintype "passive"))
    )
    (net (code "29") (name "Net-(Q10-B)") (class "Default")
      (node (ref "Q10") (pin "1") (pinfunction "B_1") (pintype "passive"))
      (node (ref "R298") (pin "2") (pinfunction "2_2") (pintype "passive"))
      (node (ref "R300") (pin "1") (pinfunction "1_1") (pintype "passive"))
    )
    (net (code "30") (name "Net-(Q10-C)") (class "Default")
      (node (ref "Q10") (pin "3") (pinfunction "C_3") (pintype "passive"))
      (node (ref "R296") (pin "1") (pinfunction "1_1") (pintype "passive"))
    )
    (net (code "31") (name "Net-(Q11-B)") (class "Default")
      (node (ref "Q11") (pin "1") (pinfunction "B_1") (pintype "passive"))
      (node (ref "R299") (pin "2") (pinfunction "2_2") (pintype "passive"))
      (node (ref "R301") (pin "1") (pinfunction "1_1") (pintype "passive"))
    )
    (net (code "32") (name "Net-(Q11-C)") (class "Default")
      (node (ref "Q11") (pin "3") (pinfunction "C_3") (pintype "passive"))
      (node (ref "R297") (pin "1") (pinfunction "1_1") (pintype "passive"))
    )
    (net (code "33") (name "Net-(R102-Pad1)") (class "Default")
      (node (ref "R102") (pin "1") (pinfunction "1_1") (pintype "passive"))
      (node (ref "R166") (pin "2") (pinfunction "2_2") (pintype "passive"))
    )
    (net (code "34") (name "Net-(R254-Pad1)") (class "Default")
      (node (ref "R254") (pin "1") (pinfunction "1_1") (pintype "passive"))
      (node (ref "R256") (pin "1") (pinfunction "1_1") (pintype "passive"))
      (node (ref "R258") (pin "2") (pinfunction "2_2") (pintype "passive"))
    )
    (net (code "35") (name "Net-(R255-Pad1)") (class "Default")
      (node (ref "R255") (pin "1") (pinfunction "1_1") (pintype "passive"))
      (node (ref "R257") (pin "1") (pinfunction "1_1") (pintype "passive"))
      (node (ref "R259") (pin "2") (pinfunction "2_2") (pintype "passive"))
    )
    (net (code "36") (name "Net-(R292-Pad1)") (class "Default")
      (node (ref "R292") (pin "1") (pinfunction "1_1") (pintype "passive"))
      (node (ref "R294") (pin "1") (pinfunction "1_1") (pintype "passive"))
      (node (ref "R296") (pin "2") (pinfunction "2_2") (pintype "passive"))
    )
    (net (code "37") (name "Net-(R293-Pad1)") (class "Default")
      (node (ref "R293") (pin "1") (pinfunction "1_1") (pintype "passive"))
      (node (ref "R295") (pin "1") (pinfunction "1_1") (pintype "passive"))
      (node (ref "R297") (pin "2") (pinfunction "2_2") (pintype "passive"))
    )
    (net (code "38") (name "Net-(U18-NR{slash}FB)") (class "Default")
      (node (ref "C131") (pin "1") (pinfunction "1_1") (pintype "passive"))
      (node (ref "R108") (pin "1") (pinfunction "1_1") (pintype "passive"))
      (node (ref "R110") (pin "2") (pinfunction "2_2") (pintype "passive"))
      (node (ref "U18") (pin "4") (pinfunction "NR/FB_4") (pintype "passive"))
    )
    (net (code "39") (name "Net-(U21-IN)") (class "Default")
      (node (ref "C101") (pin "2") (pinfunction "2_2") (pintype "passive"))
      (node (ref "L2") (pin "2") (pinfunction "2_2") (pintype "passive"))
      (node (ref "U21") (pin "1") (pinfunction "IN_1") (pintype "passive"))
    )
    (net (code "40") (name "Net-(U24-FB{slash}ADJ)") (class "Default")
      (node (ref "R101") (pin "1") (pinfunction "1_1") (pintype "passive"))
      (node (ref "R166") (pin "1") (pinfunction "1_1") (pintype "passive"))
      (node (ref "U24") (pin "3") (pinfunction "FB/ADJ_3") (pintype "passive"))
    )
    (net (code "41") (name "Net-(U26-IN)") (class "Default")
      (node (ref "C173") (pin "2") (pinfunction "2_2") (pintype "passive"))
      (node (ref "L12") (pin "2") (pinfunction "2_2") (pintype "passive"))
      (node (ref "U26") (pin "1") (pinfunction "IN_1") (pintype "passive"))
    )
    (net (code "42") (name "Net-(U30-G)") (class "Default")
      (node (ref "R256") (pin "2") (pinfunction "2_2") (pintype "passive"))
      (node (ref "U30") (pin "1") (pinfunction "G_1") (pintype "passive"))
    )
    (net (code "43") (name "Net-(U30-S)") (class "Default")
      (node (ref "C118") (pin "2") (pinfunction "2_2") (pintype "passive"))
      (node (ref "FB29") (pin "1") (pinfunction "1_1") (pintype "passive"))
      (node (ref "U30") (pin "2") (pinfunction "S_2") (pintype "passive"))
    )
    (net (code "44") (name "Net-(U31-G)") (class "Default")
      (node (ref "R257") (pin "2") (pinfunction "2_2") (pintype "passive"))
      (node (ref "U31") (pin "1") (pinfunction "G_1") (pintype "passive"))
    )
    (net (code "45") (name "Net-(U31-S)") (class "Default")
      (node (ref "C119") (pin "2") (pinfunction "2_2") (pintype "passive"))
      (node (ref "FB30") (pin "1") (pinfunction "1_1") (pintype "passive"))
      (node (ref "U31") (pin "2") (pinfunction "S_2") (pintype "passive"))
    )
    (net (code "46") (name "Net-(U33-G)") (class "Default")
      (node (ref "R294") (pin "2") (pinfunction "2_2") (pintype "passive"))
      (node (ref "U33") (pin "1") (pinfunction "G_1") (pintype "passive"))
    )
    (net (code "47") (name "Net-(U33-S)") (class "Default")
      (node (ref "C120") (pin "2") (pinfunction "2_2") (pintype "passive"))
      (node (ref "FB31") (pin "1") (pinfunction "1_1") (pintype "passive"))
      (node (ref "U33") (pin "2") (pinfunction "S_2") (pintype "passive"))
    )
    (net (code "48") (name "Net-(U34-EN)") (class "Default")
      (node (ref "R160") (pin "1") (pinfunction "1_1") (pintype "passive"))
      (node (ref "U34") (pin "5") (pinfunction "EN_5") (pintype "passive"))
    )
    (net (code "49") (name "Net-(U34-NR{slash}FB)") (class "Default")
      (node (ref "C207") (pin "1") (pinfunction "1_1") (pintype "passive"))
      (node (ref "R159") (pin "1") (pinfunction "1_1") (pintype "passive"))
      (node (ref "R163") (pin "2") (pinfunction "2_2") (pintype "passive"))
      (node (ref "U34") (pin "4") (pinfunction "NR/FB_4") (pintype "passive"))
    )
    (net (code "50") (name "Net-(U35-G)") (class "Default")
      (node (ref "R295") (pin "2") (pinfunction "2_2") (pintype "passive"))
      (node (ref "U35") (pin "1") (pinfunction "G_1") (pintype "passive"))
    )
    (net (code "51") (name "Net-(U35-S)") (class "Default")
      (node (ref "C121") (pin "2") (pinfunction "2_2") (pintype "passive"))
      (node (ref "FB32") (pin "1") (pinfunction "1_1") (pintype "passive"))
      (node (ref "U35") (pin "2") (pinfunction "S_2") (pintype "passive"))
    )
    (net (code "52") (name "SW1_24V") (class "Default")
      (node (ref "U22") (pin "3") (pinfunction "3_3") (pintype "passive"))
    )
    (net (code "53") (name "SW2_24V") (class "Default")
      (node (ref "U32") (pin "3") (pinfunction "3_3") (pintype "passive"))
    )
    (net (code "54") (name "VIN") (class "Default")
      (node (ref "D64") (pin "1") (pinfunction "A_1") (pintype "passive"))
      (node (ref "J7") (pin "1") (pinfunction "1_1") (pintype "passive"))
    )
    (net (code "55") (name "buzzer_24V") (class "Default")
      (node (ref "U30") (pin "3") (pinfunction "D_3") (pintype "passive"))
    )
    (net (code "56") (name "green_24V") (class "Default")
      (node (ref "U31") (pin "3") (pinfunction "D_3") (pintype "passive"))
    )
    (net (code "57") (name "org_24V") (class "Default")
      (node (ref "U33") (pin "3") (pinfunction "D_3") (pintype "passive"))
    )
    (net (code "58") (name "red_24V") (class "Default")
      (node (ref "U35") (pin "3") (pinfunction "D_3") (pintype "passive"))
    )
  )
)
